# MicroMod-LoRa-1W-Function-Board.net
KiCad netlist of a schematic drawn in EAGLE
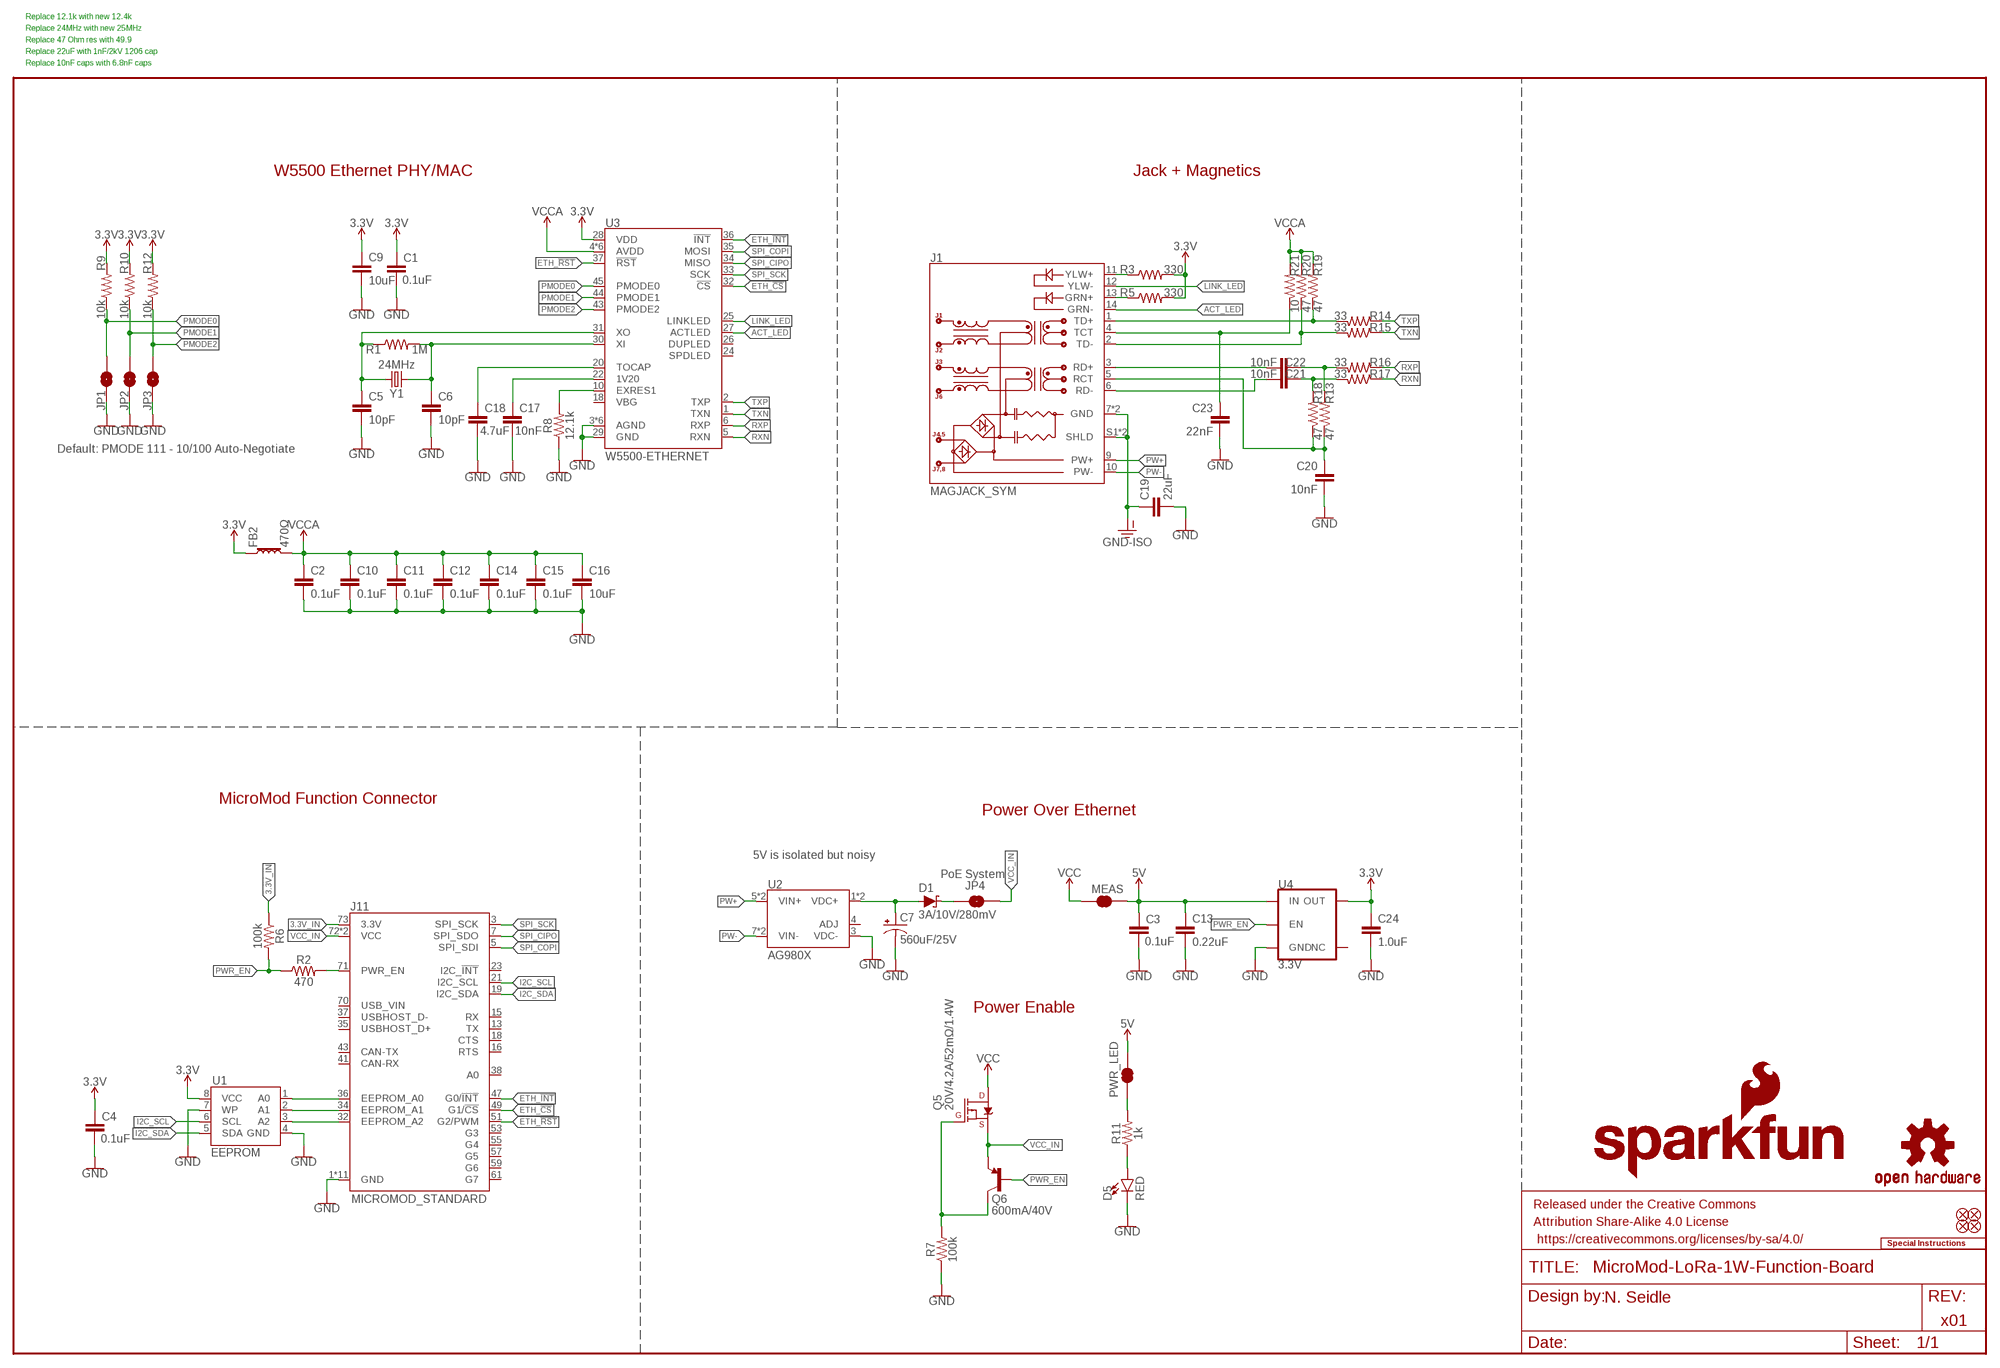
[diagram p0: schematic, sheet 1]

(export (version "E")
  (design (tool "Eeschema 10.0.6"))
  (components
    (comp (ref "C1")
      (value "0.1uF")
      (footprint "eagle-import:0603")
      (libsource (lib "eagle-import") (part "0.1UF-0603-25V-(+80/-20%)"))
    )
    (comp (ref "C2")
      (value "0.1uF")
      (footprint "eagle-import:0603")
      (libsource (lib "eagle-import") (part "0.1UF-0603-25V-5%"))
    )
    (comp (ref "C3")
      (value "0.1uF")
      (footprint "eagle-import:0603")
      (libsource (lib "eagle-import") (part "0.1UF-0603-25V-(+80/-20%)"))
    )
    (comp (ref "C4")
      (value "0.1uF")
      (footprint "eagle-import:0603")
      (libsource (lib "eagle-import") (part "0.1UF-0603-25V-(+80/-20%)"))
    )
    (comp (ref "C5")
      (value "10pF")
      (footprint "eagle-import:0603")
      (libsource (lib "eagle-import") (part "10PF-0603-50V-5%"))
    )
    (comp (ref "C6")
      (value "10pF")
      (footprint "eagle-import:0603")
      (libsource (lib "eagle-import") (part "10PF-0603-50V-5%"))
    )
    (comp (ref "C7")
      (value "560uF/25V")
      (footprint "eagle-import:PANASONIC_G")
      (libsource (lib "eagle-import") (part "560UF-PANASONIC_G-25V-20%"))
    )
    (comp (ref "C9")
      (value "10uF")
      (footprint "eagle-import:0603")
      (libsource (lib "eagle-import") (part "10UF-0603-6.3V-20%"))
    )
    (comp (ref "C10")
      (value "0.1uF")
      (footprint "eagle-import:0603")
      (libsource (lib "eagle-import") (part "0.1UF-0603-25V-5%"))
    )
    (comp (ref "C11")
      (value "0.1uF")
      (footprint "eagle-import:0603")
      (libsource (lib "eagle-import") (part "0.1UF-0603-25V-5%"))
    )
    (comp (ref "C12")
      (value "0.1uF")
      (footprint "eagle-import:0603")
      (libsource (lib "eagle-import") (part "0.1UF-0603-25V-5%"))
    )
    (comp (ref "C13")
      (value "0.22uF")
      (footprint "eagle-import:0603")
      (libsource (lib "eagle-import") (part "0.22UF-0603-25V-10%"))
    )
    (comp (ref "C14")
      (value "0.1uF")
      (footprint "eagle-import:0603")
      (libsource (lib "eagle-import") (part "0.1UF-0603-25V-5%"))
    )
    (comp (ref "C15")
      (value "0.1uF")
      (footprint "eagle-import:0603")
      (libsource (lib "eagle-import") (part "0.1UF-0603-25V-5%"))
    )
    (comp (ref "C16")
      (value "10uF")
      (footprint "eagle-import:0603")
      (libsource (lib "eagle-import") (part "10UF-0603-6.3V-20%"))
    )
    (comp (ref "C17")
      (value "10nF")
      (footprint "eagle-import:0603")
      (libsource (lib "eagle-import") (part "10NF-0603-50V-10%"))
    )
    (comp (ref "C18")
      (value "4.7uF")
      (footprint "eagle-import:0603")
      (libsource (lib "eagle-import") (part "4.7UF-0603-6.3V-(10%)"))
    )
    (comp (ref "C19")
      (value "22uF")
      (footprint "eagle-import:1206")
      (libsource (lib "eagle-import") (part "22UF-1206-50V-10%"))
    )
    (comp (ref "C20")
      (value "10nF")
      (footprint "eagle-import:0603")
      (libsource (lib "eagle-import") (part "10NF-0603-50V-10%"))
    )
    (comp (ref "C21")
      (value "10nF")
      (footprint "eagle-import:0603")
      (libsource (lib "eagle-import") (part "10NF-0603-50V-10%"))
    )
    (comp (ref "C22")
      (value "10nF")
      (footprint "eagle-import:0603")
      (libsource (lib "eagle-import") (part "10NF-0603-50V-10%"))
    )
    (comp (ref "C23")
      (value "22nF")
      (footprint "eagle-import:0603")
      (libsource (lib "eagle-import") (part "22NF/22,000PF-0603-50V-10%"))
    )
    (comp (ref "C24")
      (value "1.0uF")
      (footprint "eagle-import:0603")
      (libsource (lib "eagle-import") (part "1.0UF-0603-16V-10%-X7R"))
    )
    (comp (ref "D1")
      (value "3A/10V/280mV")
      (footprint "eagle-import:SOD-323")
      (libsource (lib "eagle-import") (part "DIODE-SCHOTTKY-BAT60A"))
    )
    (comp (ref "D5")
      (value "RED")
      (footprint "eagle-import:LED-0603")
      (libsource (lib "eagle-import") (part "LED-RED0603"))
    )
    (comp (ref "FB2")
      (value "470Ω")
      (footprint "eagle-import:0603")
      (libsource (lib "eagle-import") (part "FERRITE_BEAD-0603-470Ω-100MHZ-1A-200MILIΩ"))
    )
    (comp (ref "FD1")
      (value "FIDUCIALUFIDUCIAL")
      (footprint "eagle-import:FIDUCIAL-MICRO")
      (libsource (lib "eagle-import") (part "FIDUCIALUFIDUCIAL"))
    )
    (comp (ref "FD2")
      (value "FIDUCIALUFIDUCIAL")
      (footprint "eagle-import:FIDUCIAL-MICRO")
      (libsource (lib "eagle-import") (part "FIDUCIALUFIDUCIAL"))
    )
    (comp (ref "FD3")
      (value "FIDUCIALUFIDUCIAL")
      (footprint "eagle-import:FIDUCIAL-MICRO")
      (libsource (lib "eagle-import") (part "FIDUCIALUFIDUCIAL"))
    )
    (comp (ref "FD4")
      (value "FIDUCIALUFIDUCIAL")
      (footprint "eagle-import:FIDUCIAL-MICRO")
      (libsource (lib "eagle-import") (part "FIDUCIALUFIDUCIAL"))
    )
    (comp (ref "FRAME1")
      (value "FRAME-LEDGER")
      (footprint "eagle-import:CREATIVE_COMMONS")
      (libsource (lib "eagle-import") (part "FRAME-LEDGER"))
    )
    (comp (ref "J1")
      (value "MAGJACK_SYM")
      (footprint "eagle-import:MAGJACK-STR_LED")
      (libsource (lib "eagle-import") (part "MAGJACK_SYM"))
    )
    (comp (ref "J11")
      (value "MICROMOD_STANDARD")
      (footprint "eagle-import:M.2-CARD-E-22_FUNCTION_STANDARD")
      (libsource (lib "eagle-import") (part "MICROMOD_STANDARD"))
    )
    (comp (ref "JP1")
      (value "JUMPER-SMT_2_NO_SILK")
      (footprint "eagle-import:SMT-JUMPER_2_NO_SILK")
      (libsource (lib "eagle-import") (part "JUMPER-SMT_2_NO_SILK"))
    )
    (comp (ref "JP2")
      (value "JUMPER-SMT_2_NO_SILK")
      (footprint "eagle-import:SMT-JUMPER_2_NO_SILK")
      (libsource (lib "eagle-import") (part "JUMPER-SMT_2_NO_SILK"))
    )
    (comp (ref "JP3")
      (value "JUMPER-SMT_2_NO_SILK")
      (footprint "eagle-import:SMT-JUMPER_2_NO_SILK")
      (libsource (lib "eagle-import") (part "JUMPER-SMT_2_NO_SILK"))
    )
    (comp (ref "JP4")
      (value "PoE System")
      (footprint "eagle-import:SMT-JUMPER_2_NO_SILK")
      (libsource (lib "eagle-import") (part "JUMPER-SMT_2_NO_SILK"))
    )
    (comp (ref "LOGO1")
      (value "SFE_LOGO_NAME_FLAME.1_INCH")
      (footprint "eagle-import:SFE_LOGO_NAME_FLAME_.1")
      (libsource (lib "eagle-import") (part "SFE_LOGO_NAME_FLAME.1_INCH"))
    )
    (comp (ref "LOGO2")
      (value "SPECIAL_INSTRUCTIONS-ORDERING")
      (footprint "eagle-import:ORDERING_INSTRUCTIONS")
      (libsource (lib "eagle-import") (part "SPECIAL_INSTRUCTIONS-ORDERING"))
    )
    (comp (ref "LOGO3")
      (value "OSHW-LOGOMINI")
      (footprint "eagle-import:OSHW-LOGO-MINI")
      (libsource (lib "eagle-import") (part "OSHW-LOGOMINI"))
    )
    (comp (ref "MEAS")
      (value "JUMPER-COMBO_2_NC_TRACE")
      (footprint "eagle-import:COMBO-JUMPER_2_NC_TRACE")
      (libsource (lib "eagle-import") (part "JUMPER-COMBO_2_NC_TRACE"))
    )
    (comp (ref "PWR_LED")
      (value "JUMPER-SMT_2_NC_TRACE_SILK")
      (footprint "eagle-import:SMT-JUMPER_2_NC_TRACE_SILK")
      (libsource (lib "eagle-import") (part "JUMPER-SMT_2_NC_TRACE_SILK"))
    )
    (comp (ref "Q5")
      (value "20V/4.2A/52mΩ/1.4W")
      (footprint "eagle-import:SOT23-3")
      (libsource (lib "eagle-import") (part "MOSFET_PCH-DMG2305UX-7"))
    )
    (comp (ref "Q6")
      (value "600mA/40V")
      (footprint "eagle-import:SOT23-3")
      (libsource (lib "eagle-import") (part "TRANS_PNP-MMBT4403"))
    )
    (comp (ref "R1")
      (value "1M")
      (footprint "eagle-import:0603")
      (libsource (lib "eagle-import") (part "1MOHM-0603-1/4W-5%"))
    )
    (comp (ref "R2")
      (value "470")
      (footprint "eagle-import:0603")
      (libsource (lib "eagle-import") (part "470OHM-0603-1/10W-1%"))
    )
    (comp (ref "R3")
      (value "330")
      (footprint "eagle-import:0603")
      (libsource (lib "eagle-import") (part "330OHM-0603-1/10W-1%"))
    )
    (comp (ref "R5")
      (value "330")
      (footprint "eagle-import:0603")
      (libsource (lib "eagle-import") (part "330OHM-0603-1/10W-1%"))
    )
    (comp (ref "R6")
      (value "100k")
      (footprint "eagle-import:0603")
      (libsource (lib "eagle-import") (part "100KOHM-0603-1/10W-1%"))
    )
    (comp (ref "R7")
      (value "100k")
      (footprint "eagle-import:0603")
      (libsource (lib "eagle-import") (part "100KOHM-0603-1/10W-1%"))
    )
    (comp (ref "R8")
      (value "12.1k")
      (footprint "eagle-import:0603")
      (libsource (lib "eagle-import") (part "12.1KOHM-0603-1/10W-1%"))
    )
    (comp (ref "R9")
      (value "10k")
      (footprint "eagle-import:0603")
      (libsource (lib "eagle-import") (part "10KOHM-0603-1/10W-1%"))
    )
    (comp (ref "R10")
      (value "10k")
      (footprint "eagle-import:0603")
      (libsource (lib "eagle-import") (part "10KOHM-0603-1/10W-1%"))
    )
    (comp (ref "R11")
      (value "1k")
      (footprint "eagle-import:0603")
      (libsource (lib "eagle-import") (part "1KOHM-0603-1/10W-1%"))
    )
    (comp (ref "R12")
      (value "10k")
      (footprint "eagle-import:0603")
      (libsource (lib "eagle-import") (part "10KOHM-0603-1/10W-1%"))
    )
    (comp (ref "R13")
      (value "47")
      (footprint "eagle-import:0603")
      (libsource (lib "eagle-import") (part "47OHM-0603-1/10W-1%"))
    )
    (comp (ref "R14")
      (value "33")
      (footprint "eagle-import:0603")
      (libsource (lib "eagle-import") (part "33OHM-0603-1/10W-1%"))
    )
    (comp (ref "R15")
      (value "33")
      (footprint "eagle-import:0603")
      (libsource (lib "eagle-import") (part "33OHM-0603-1/10W-1%"))
    )
    (comp (ref "R16")
      (value "33")
      (footprint "eagle-import:0603")
      (libsource (lib "eagle-import") (part "33OHM-0603-1/10W-1%"))
    )
    (comp (ref "R17")
      (value "33")
      (footprint "eagle-import:0603")
      (libsource (lib "eagle-import") (part "33OHM-0603-1/10W-1%"))
    )
    (comp (ref "R18")
      (value "47")
      (footprint "eagle-import:0603")
      (libsource (lib "eagle-import") (part "47OHM-0603-1/10W-1%"))
    )
    (comp (ref "R19")
      (value "47")
      (footprint "eagle-import:0603")
      (libsource (lib "eagle-import") (part "47OHM-0603-1/10W-1%"))
    )
    (comp (ref "R20")
      (value "47")
      (footprint "eagle-import:0603")
      (libsource (lib "eagle-import") (part "47OHM-0603-1/10W-1%"))
    )
    (comp (ref "R21")
      (value "10")
      (footprint "eagle-import:0603")
      (libsource (lib "eagle-import") (part "10OHM-0603-1/10W-1%"))
    )
    (comp (ref "U1")
      (value "EEPROM")
      (footprint "eagle-import:SO08")
      (libsource (lib "eagle-import") (part "EEPROM-I2C512K"))
    )
    (comp (ref "U2")
      (value "AG980X")
      (footprint "eagle-import:AG980X")
      (libsource (lib "eagle-import") (part "AG980X"))
    )
    (comp (ref "U3")
      (value "W5500-ETHERNET")
      (footprint "eagle-import:LQFP-48")
      (libsource (lib "eagle-import") (part "W5500-ETHERNET"))
    )
    (comp (ref "U4")
      (value "3.3V")
      (footprint "eagle-import:SOT23-5")
      (libsource (lib "eagle-import") (part "V_REG_AP2112K-3.3V"))
    )
    (comp (ref "Y1")
      (value "24MHz")
      (footprint "eagle-import:CRYSTAL-SMD-2.0X1.6MM")
      (libsource (lib "eagle-import") (part "CRYSTAL-24MHZ-SMD-2.0X1.6MM"))
    )
  )
  (nets
    (net (code "1") (name "/ETH_~{CS}") (class "Default")
      (node (ref "J11") (pin "49") (pinfunction "G1/~{CS}_49") (pintype "bidirectional"))
      (node (ref "U3") (pin "32") (pinfunction "~{CS}_32") (pintype "bidirectional"))
    )
    (net (code "2") (name "/ETH_~{INT}") (class "Default")
      (node (ref "J11") (pin "47") (pinfunction "G0/~{INT}_47") (pintype "bidirectional"))
      (node (ref "U3") (pin "36") (pinfunction "~{INT}_36") (pintype "bidirectional"))
    )
    (net (code "3") (name "/ETH_~{RST}") (class "Default")
      (node (ref "J11") (pin "51") (pinfunction "G2/PWM_51") (pintype "bidirectional"))
      (node (ref "U3") (pin "37") (pinfunction "~{RST}_37") (pintype "bidirectional"))
    )
    (net (code "4") (name "3.3V") (class "Default")
      (node (ref "C1") (pin "1") (pinfunction "1_1") (pintype "passive"))
      (node (ref "C24") (pin "1") (pinfunction "1_1") (pintype "passive"))
      (node (ref "C4") (pin "1") (pinfunction "1_1") (pintype "passive"))
      (node (ref "C9") (pin "1") (pinfunction "1_1") (pintype "passive"))
      (node (ref "FB2") (pin "1") (pinfunction "1_1") (pintype "passive"))
      (node (ref "R10") (pin "2") (pinfunction "2_2") (pintype "passive"))
      (node (ref "R12") (pin "2") (pinfunction "2_2") (pintype "passive"))
      (node (ref "R3") (pin "2") (pinfunction "2_2") (pintype "passive"))
      (node (ref "R5") (pin "2") (pinfunction "2_2") (pintype "passive"))
      (node (ref "R9") (pin "2") (pinfunction "2_2") (pintype "passive"))
      (node (ref "U1") (pin "8") (pinfunction "VCC_8") (pintype "power_in"))
      (node (ref "U3") (pin "28") (pinfunction "VDD_28") (pintype "bidirectional"))
      (node (ref "U4") (pin "5") (pinfunction "OUT_5") (pintype "passive"))
    )
    (net (code "5") (name "3.3V_IN") (class "Default")
      (node (ref "J11") (pin "73") (pinfunction "3.3V_73") (pintype "bidirectional"))
      (node (ref "R6") (pin "1") (pinfunction "1_1") (pintype "passive"))
    )
    (net (code "6") (name "5V") (class "Default")
      (node (ref "C13") (pin "1") (pinfunction "1_1") (pintype "passive"))
      (node (ref "C3") (pin "1") (pinfunction "1_1") (pintype "passive"))
      (node (ref "MEAS") (pin "2") (pinfunction "2_2") (pintype "passive"))
      (node (ref "MEAS") (pin "4") (pinfunction "2_4") (pintype "passive"))
      (node (ref "PWR_LED") (pin "2") (pinfunction "2_2") (pintype "passive"))
      (node (ref "U4") (pin "1") (pinfunction "IN_1") (pintype "input"))
    )
    (net (code "7") (name "ACT_LED") (class "Default")
      (node (ref "J1") (pin "14") (pinfunction "GRN-_14") (pintype "bidirectional"))
      (node (ref "U3") (pin "27") (pinfunction "ACTLED_27") (pintype "bidirectional"))
    )
    (net (code "8") (name "GND") (class "Default")
      (node (ref "C1") (pin "2") (pinfunction "2_2") (pintype "passive"))
      (node (ref "C10") (pin "2") (pinfunction "2_2") (pintype "passive"))
      (node (ref "C11") (pin "2") (pinfunction "2_2") (pintype "passive"))
      (node (ref "C12") (pin "2") (pinfunction "2_2") (pintype "passive"))
      (node (ref "C13") (pin "2") (pinfunction "2_2") (pintype "passive"))
      (node (ref "C14") (pin "2") (pinfunction "2_2") (pintype "passive"))
      (node (ref "C15") (pin "2") (pinfunction "2_2") (pintype "passive"))
      (node (ref "C16") (pin "2") (pinfunction "2_2") (pintype "passive"))
      (node (ref "C17") (pin "2") (pinfunction "2_2") (pintype "passive"))
      (node (ref "C18") (pin "2") (pinfunction "2_2") (pintype "passive"))
      (node (ref "C19") (pin "2") (pinfunction "2_2") (pintype "passive"))
      (node (ref "C2") (pin "2") (pinfunction "2_2") (pintype "passive"))
      (node (ref "C20") (pin "2") (pinfunction "2_2") (pintype "passive"))
      (node (ref "C23") (pin "2") (pinfunction "2_2") (pintype "passive"))
      (node (ref "C24") (pin "2") (pinfunction "2_2") (pintype "passive"))
      (node (ref "C3") (pin "2") (pinfunction "2_2") (pintype "passive"))
      (node (ref "C4") (pin "2") (pinfunction "2_2") (pintype "passive"))
      (node (ref "C5") (pin "2") (pinfunction "2_2") (pintype "passive"))
      (node (ref "C6") (pin "2") (pinfunction "2_2") (pintype "passive"))
      (node (ref "C7") (pin "-") (pinfunction "-_-") (pintype "passive"))
      (node (ref "C9") (pin "2") (pinfunction "2_2") (pintype "passive"))
      (node (ref "D5") (pin "C") (pinfunction "C_C") (pintype "passive"))
      (node (ref "J11") (pin "1") (pinfunction "GND_1") (pintype "bidirectional"))
      (node (ref "J11") (pin "33") (pinfunction "GND_33") (pintype "bidirectional"))
      (node (ref "J11") (pin "39") (pinfunction "GND_39") (pintype "bidirectional"))
      (node (ref "J11") (pin "45") (pinfunction "GND_45") (pintype "bidirectional"))
      (node (ref "J11") (pin "75") (pinfunction "GND_75") (pintype "bidirectional"))
      (node (ref "J11") (pin "GND1") (pinfunction "GND_GND1") (pintype "bidirectional"))
      (node (ref "J11") (pin "GND2") (pinfunction "GND_GND2") (pintype "bidirectional"))
      (node (ref "J11") (pin "GND3") (pinfunction "GND_GND3") (pintype "bidirectional"))
      (node (ref "J11") (pin "GND4") (pinfunction "GND_GND4") (pintype "bidirectional"))
      (node (ref "J11") (pin "GND5") (pinfunction "GND_GND5") (pintype "bidirectional"))
      (node (ref "J11") (pin "GND6") (pinfunction "GND_GND6") (pintype "bidirectional"))
      (node (ref "JP1") (pin "1") (pinfunction "1_1") (pintype "passive"))
      (node (ref "JP2") (pin "1") (pinfunction "1_1") (pintype "passive"))
      (node (ref "JP3") (pin "1") (pinfunction "1_1") (pintype "passive"))
      (node (ref "R7") (pin "1") (pinfunction "1_1") (pintype "passive"))
      (node (ref "R8") (pin "1") (pinfunction "1_1") (pintype "passive"))
      (node (ref "U1") (pin "4") (pinfunction "GND_4") (pintype "power_in"))
      (node (ref "U1") (pin "7") (pinfunction "WP_7") (pintype "bidirectional"))
      (node (ref "U2") (pin "3") (pinfunction "VDC-_3") (pintype "bidirectional"))
      (node (ref "U3") (pin "14") (pinfunction "AGND_14") (pintype "bidirectional"))
      (node (ref "U3") (pin "16") (pinfunction "AGND_16") (pintype "bidirectional"))
      (node (ref "U3") (pin "19") (pinfunction "AGND_19") (pintype "bidirectional"))
      (node (ref "U3") (pin "29") (pinfunction "GND_29") (pintype "bidirectional"))
      (node (ref "U3") (pin "3") (pinfunction "AGND_3") (pintype "bidirectional"))
      (node (ref "U3") (pin "48") (pinfunction "AGND_48") (pintype "bidirectional"))
      (node (ref "U3") (pin "9") (pinfunction "AGND_9") (pintype "bidirectional"))
      (node (ref "U4") (pin "2") (pinfunction "GND_2") (pintype "input"))
    )
    (net (code "9") (name "GND-ISO") (class "Default")
      (node (ref "C19") (pin "1") (pinfunction "1_1") (pintype "passive"))
      (node (ref "J1") (pin "7") (pinfunction "GND_7") (pintype "bidirectional"))
      (node (ref "J1") (pin "8") (pinfunction "GND_8") (pintype "bidirectional"))
      (node (ref "J1") (pin "S1") (pinfunction "SHLD_S1") (pintype "bidirectional"))
      (node (ref "J1") (pin "S2") (pinfunction "SHLD_S2") (pintype "bidirectional"))
    )
    (net (code "10") (name "I2C_SCL") (class "Default")
      (node (ref "J11") (pin "21") (pinfunction "I2C_SCL_21") (pintype "bidirectional"))
      (node (ref "U1") (pin "6") (pinfunction "SCL_6") (pintype "bidirectional"))
    )
    (net (code "11") (name "I2C_SDA") (class "Default")
      (node (ref "J11") (pin "19") (pinfunction "I2C_SDA_19") (pintype "bidirectional"))
      (node (ref "U1") (pin "5") (pinfunction "SDA_5") (pintype "bidirectional"))
    )
    (net (code "12") (name "LINK_LED") (class "Default")
      (node (ref "J1") (pin "12") (pinfunction "YLW-_12") (pintype "bidirectional"))
      (node (ref "U3") (pin "25") (pinfunction "LINKLED_25") (pintype "bidirectional"))
    )
    (net (code "13") (name "Net-(C7-Pad+)") (class "Default")
      (node (ref "C7") (pin "+") (pinfunction "+_+") (pintype "passive"))
      (node (ref "D1") (pin "A") (pinfunction "A_A") (pintype "passive"))
      (node (ref "U2") (pin "1") (pinfunction "VDC+_1") (pintype "bidirectional"))
      (node (ref "U2") (pin "2") (pinfunction "VDC+_2") (pintype "bidirectional"))
    )
    (net (code "14") (name "Net-(C21-Pad1)") (class "Default")
      (node (ref "C21") (pin "1") (pinfunction "1_1") (pintype "passive"))
      (node (ref "R17") (pin "2") (pinfunction "2_2") (pintype "passive"))
      (node (ref "R18") (pin "2") (pinfunction "2_2") (pintype "passive"))
    )
    (net (code "15") (name "Net-(C22-Pad1)") (class "Default")
      (node (ref "C22") (pin "1") (pinfunction "1_1") (pintype "passive"))
      (node (ref "R13") (pin "2") (pinfunction "2_2") (pintype "passive"))
      (node (ref "R16") (pin "2") (pinfunction "2_2") (pintype "passive"))
    )
    (net (code "16") (name "Net-(D1-PadC)") (class "Default")
      (node (ref "D1") (pin "C") (pinfunction "C_C") (pintype "passive"))
      (node (ref "JP4") (pin "1") (pinfunction "1_1") (pintype "passive"))
    )
    (net (code "17") (name "Net-(D5-PadA)") (class "Default")
      (node (ref "D5") (pin "A") (pinfunction "A_A") (pintype "passive"))
      (node (ref "R11") (pin "1") (pinfunction "1_1") (pintype "passive"))
    )
    (net (code "18") (name "Net-(J1-GRN+)") (class "Default")
      (node (ref "J1") (pin "13") (pinfunction "GRN+_13") (pintype "bidirectional"))
      (node (ref "R5") (pin "1") (pinfunction "1_1") (pintype "passive"))
    )
    (net (code "19") (name "Net-(J1-RCT)") (class "Default")
      (node (ref "C20") (pin "1") (pinfunction "1_1") (pintype "passive"))
      (node (ref "J1") (pin "5") (pinfunction "RCT_5") (pintype "bidirectional"))
      (node (ref "R13") (pin "1") (pinfunction "1_1") (pintype "passive"))
      (node (ref "R18") (pin "1") (pinfunction "1_1") (pintype "passive"))
    )
    (net (code "20") (name "Net-(J1-RD+)") (class "Default")
      (node (ref "C22") (pin "2") (pinfunction "2_2") (pintype "passive"))
      (node (ref "J1") (pin "3") (pinfunction "RD+_3") (pintype "bidirectional"))
    )
    (net (code "21") (name "Net-(J1-RD-)") (class "Default")
      (node (ref "C21") (pin "2") (pinfunction "2_2") (pintype "passive"))
      (node (ref "J1") (pin "6") (pinfunction "RD-_6") (pintype "bidirectional"))
    )
    (net (code "22") (name "Net-(J1-TCT)") (class "Default")
      (node (ref "C23") (pin "1") (pinfunction "1_1") (pintype "passive"))
      (node (ref "J1") (pin "4") (pinfunction "TCT_4") (pintype "bidirectional"))
      (node (ref "R21") (pin "1") (pinfunction "1_1") (pintype "passive"))
    )
    (net (code "23") (name "Net-(J1-TD+)") (class "Default")
      (node (ref "J1") (pin "1") (pinfunction "TD+_1") (pintype "bidirectional"))
      (node (ref "R14") (pin "2") (pinfunction "2_2") (pintype "passive"))
      (node (ref "R19") (pin "1") (pinfunction "1_1") (pintype "passive"))
    )
    (net (code "24") (name "Net-(J1-TD-)") (class "Default")
      (node (ref "J1") (pin "2") (pinfunction "TD-_2") (pintype "bidirectional"))
      (node (ref "R15") (pin "2") (pinfunction "2_2") (pintype "passive"))
      (node (ref "R20") (pin "1") (pinfunction "1_1") (pintype "passive"))
    )
    (net (code "25") (name "Net-(J1-YLW+)") (class "Default")
      (node (ref "J1") (pin "11") (pinfunction "YLW+_11") (pintype "bidirectional"))
      (node (ref "R3") (pin "1") (pinfunction "1_1") (pintype "passive"))
    )
    (net (code "26") (name "Net-(J11-EEPROM_A0)") (class "Default")
      (node (ref "J11") (pin "36") (pinfunction "EEPROM_A0_36") (pintype "bidirectional"))
      (node (ref "U1") (pin "1") (pinfunction "A0_1") (pintype "bidirectional"))
    )
    (net (code "27") (name "Net-(J11-EEPROM_A1)") (class "Default")
      (node (ref "J11") (pin "34") (pinfunction "EEPROM_A1_34") (pintype "bidirectional"))
      (node (ref "U1") (pin "2") (pinfunction "A1_2") (pintype "bidirectional"))
    )
    (net (code "28") (name "Net-(J11-EEPROM_A2)") (class "Default")
      (node (ref "J11") (pin "32") (pinfunction "EEPROM_A2_32") (pintype "bidirectional"))
      (node (ref "U1") (pin "3") (pinfunction "A2_3") (pintype "bidirectional"))
    )
    (net (code "29") (name "Net-(J11-PWR_EN)") (class "Default")
      (node (ref "J11") (pin "71") (pinfunction "PWR_EN_71") (pintype "bidirectional"))
      (node (ref "R2") (pin "2") (pinfunction "2_2") (pintype "passive"))
    )
    (net (code "30") (name "Net-(PWR_LED-Pad1)") (class "Default")
      (node (ref "PWR_LED") (pin "1") (pinfunction "1_1") (pintype "passive"))
      (node (ref "R11") (pin "2") (pinfunction "2_2") (pintype "passive"))
    )
    (net (code "31") (name "Net-(Q5-G)") (class "Default")
      (node (ref "Q5") (pin "1") (pinfunction "G_1") (pintype "bidirectional"))
      (node (ref "Q6") (pin "3") (pinfunction "C_3") (pintype "passive"))
      (node (ref "R7") (pin "2") (pinfunction "2_2") (pintype "passive"))
    )
    (net (code "32") (name "Net-(U3-1V20)") (class "Default")
      (node (ref "C17") (pin "1") (pinfunction "1_1") (pintype "passive"))
      (node (ref "U3") (pin "22") (pinfunction "1V20_22") (pintype "bidirectional"))
    )
    (net (code "33") (name "Net-(U3-EXRES1)") (class "Default")
      (node (ref "R8") (pin "2") (pinfunction "2_2") (pintype "passive"))
      (node (ref "U3") (pin "10") (pinfunction "EXRES1_10") (pintype "bidirectional"))
    )
    (net (code "34") (name "Net-(U3-TOCAP)") (class "Default")
      (node (ref "C18") (pin "1") (pinfunction "1_1") (pintype "passive"))
      (node (ref "U3") (pin "20") (pinfunction "TOCAP_20") (pintype "bidirectional"))
    )
    (net (code "35") (name "Net-(U3-XI)") (class "Default")
      (node (ref "C6") (pin "1") (pinfunction "1_1") (pintype "passive"))
      (node (ref "R1") (pin "2") (pinfunction "2_2") (pintype "passive"))
      (node (ref "U3") (pin "30") (pinfunction "XI_30") (pintype "bidirectional"))
      (node (ref "Y1") (pin "3") (pinfunction "2_3") (pintype "passive"))
    )
    (net (code "36") (name "Net-(U3-XO)") (class "Default")
      (node (ref "C5") (pin "1") (pinfunction "1_1") (pintype "passive"))
      (node (ref "R1") (pin "1") (pinfunction "1_1") (pintype "passive"))
      (node (ref "U3") (pin "31") (pinfunction "XO_31") (pintype "bidirectional"))
      (node (ref "Y1") (pin "1") (pinfunction "1_1") (pintype "passive"))
    )
    (net (code "37") (name "PMODE0") (class "Default")
      (node (ref "JP1") (pin "2") (pinfunction "2_2") (pintype "passive"))
      (node (ref "R9") (pin "1") (pinfunction "1_1") (pintype "passive"))
      (node (ref "U3") (pin "45") (pinfunction "PMODE0_45") (pintype "bidirectional"))
    )
    (net (code "38") (name "PMODE1") (class "Default")
      (node (ref "JP2") (pin "2") (pinfunction "2_2") (pintype "passive"))
      (node (ref "R10") (pin "1") (pinfunction "1_1") (pintype "passive"))
      (node (ref "U3") (pin "44") (pinfunction "PMODE1_44") (pintype "bidirectional"))
    )
    (net (code "39") (name "PMODE2") (class "Default")
      (node (ref "JP3") (pin "2") (pinfunction "2_2") (pintype "passive"))
      (node (ref "R12") (pin "1") (pinfunction "1_1") (pintype "passive"))
      (node (ref "U3") (pin "43") (pinfunction "PMODE2_43") (pintype "bidirectional"))
    )
    (net (code "40") (name "PW+") (class "Default")
      (node (ref "J1") (pin "9") (pinfunction "PW+_9") (pintype "bidirectional"))
      (node (ref "U2") (pin "5") (pinfunction "VIN+_5") (pintype "bidirectional"))
      (node (ref "U2") (pin "6") (pinfunction "VIN+_6") (pintype "bidirectional"))
    )
    (net (code "41") (name "PW-") (class "Default")
      (node (ref "J1") (pin "10") (pinfunction "PW-_10") (pintype "bidirectional"))
      (node (ref "U2") (pin "7") (pinfunction "VIN-_7") (pintype "bidirectional"))
      (node (ref "U2") (pin "8") (pinfunction "VIN-_8") (pintype "bidirectional"))
    )
    (net (code "42") (name "PWR_EN") (class "Default")
      (node (ref "Q6") (pin "1") (pinfunction "B_1") (pintype "passive"))
      (node (ref "R2") (pin "1") (pinfunction "1_1") (pintype "passive"))
      (node (ref "R6") (pin "2") (pinfunction "2_2") (pintype "passive"))
      (node (ref "U4") (pin "3") (pinfunction "EN_3") (pintype "input"))
    )
    (net (code "43") (name "RXN") (class "Default")
      (node (ref "R17") (pin "1") (pinfunction "1_1") (pintype "passive"))
      (node (ref "U3") (pin "5") (pinfunction "RXN_5") (pintype "bidirectional"))
    )
    (net (code "44") (name "RXP") (class "Default")
      (node (ref "R16") (pin "1") (pinfunction "1_1") (pintype "passive"))
      (node (ref "U3") (pin "6") (pinfunction "RXP_6") (pintype "bidirectional"))
    )
    (net (code "45") (name "SPI_CIPO") (class "Default")
      (node (ref "J11") (pin "7") (pinfunction "SPI_SDO_7") (pintype "bidirectional"))
      (node (ref "U3") (pin "34") (pinfunction "MISO_34") (pintype "bidirectional"))
    )
    (net (code "46") (name "SPI_COPI") (class "Default")
      (node (ref "J11") (pin "5") (pinfunction "SPI_SDI_5") (pintype "bidirectional"))
      (node (ref "U3") (pin "35") (pinfunction "MOSI_35") (pintype "bidirectional"))
    )
    (net (code "47") (name "SPI_SCK") (class "Default")
      (node (ref "J11") (pin "3") (pinfunction "SPI_SCK_3") (pintype "bidirectional"))
      (node (ref "U3") (pin "33") (pinfunction "SCK_33") (pintype "bidirectional"))
    )
    (net (code "48") (name "TXN") (class "Default")
      (node (ref "R15") (pin "1") (pinfunction "1_1") (pintype "passive"))
      (node (ref "U3") (pin "1") (pinfunction "TXN_1") (pintype "bidirectional"))
    )
    (net (code "49") (name "TXP") (class "Default")
      (node (ref "R14") (pin "1") (pinfunction "1_1") (pintype "passive"))
      (node (ref "U3") (pin "2") (pinfunction "TXP_2") (pintype "bidirectional"))
    )
    (net (code "50") (name "VCC") (class "Default")
      (node (ref "MEAS") (pin "1") (pinfunction "1_1") (pintype "passive"))
      (node (ref "MEAS") (pin "3") (pinfunction "1_3") (pintype "passive"))
      (node (ref "Q5") (pin "3") (pinfunction "D_3") (pintype "bidirectional"))
    )
    (net (code "51") (name "VCCA") (class "Default")
      (node (ref "C10") (pin "1") (pinfunction "1_1") (pintype "passive"))
      (node (ref "C11") (pin "1") (pinfunction "1_1") (pintype "passive"))
      (node (ref "C12") (pin "1") (pinfunction "1_1") (pintype "passive"))
      (node (ref "C14") (pin "1") (pinfunction "1_1") (pintype "passive"))
      (node (ref "C15") (pin "1") (pinfunction "1_1") (pintype "passive"))
      (node (ref "C16") (pin "1") (pinfunction "1_1") (pintype "passive"))
      (node (ref "C2") (pin "1") (pinfunction "1_1") (pintype "passive"))
      (node (ref "FB2") (pin "2") (pinfunction "2_2") (pintype "passive"))
      (node (ref "R19") (pin "2") (pinfunction "2_2") (pintype "passive"))
      (node (ref "R20") (pin "2") (pinfunction "2_2") (pintype "passive"))
      (node (ref "R21") (pin "2") (pinfunction "2_2") (pintype "passive"))
      (node (ref "U3") (pin "11") (pinfunction "AVDD_11") (pintype "bidirectional"))
      (node (ref "U3") (pin "15") (pinfunction "AVDD_15") (pintype "bidirectional"))
      (node (ref "U3") (pin "17") (pinfunction "AVDD_17") (pintype "bidirectional"))
      (node (ref "U3") (pin "21") (pinfunction "AVDD_21") (pintype "bidirectional"))
      (node (ref "U3") (pin "4") (pinfunction "AVDD_4") (pintype "bidirectional"))
      (node (ref "U3") (pin "8") (pinfunction "AVDD_8") (pintype "bidirectional"))
    )
    (net (code "52") (name "VCC_IN") (class "Default")
      (node (ref "J11") (pin "72") (pinfunction "VCC_72") (pintype "bidirectional"))
      (node (ref "J11") (pin "74") (pinfunction "VCC_74") (pintype "bidirectional"))
      (node (ref "JP4") (pin "2") (pinfunction "2_2") (pintype "passive"))
      (node (ref "Q5") (pin "2") (pinfunction "S_2") (pintype "bidirectional"))
      (node (ref "Q6") (pin "2") (pinfunction "E_2") (pintype "passive"))
    )
    (net (code "53") (name "unconnected-(J11-A0-Pad38)") (class "Default")
      (node (ref "J11") (pin "38") (pinfunction "A0_38") (pintype "bidirectional"))
    )
    (net (code "54") (name "unconnected-(J11-CAN-RX-Pad41)") (class "Default")
      (node (ref "J11") (pin "41") (pinfunction "CAN-RX_41") (pintype "bidirectional"))
    )
    (net (code "55") (name "unconnected-(J11-CAN-TX-Pad43)") (class "Default")
      (node (ref "J11") (pin "43") (pinfunction "CAN-TX_43") (pintype "bidirectional"))
    )
    (net (code "56") (name "unconnected-(J11-CTS-Pad18)") (class "Default")
      (node (ref "J11") (pin "18") (pinfunction "CTS_18") (pintype "bidirectional"))
    )
    (net (code "57") (name "unconnected-(J11-G3-Pad53)") (class "Default")
      (node (ref "J11") (pin "53") (pinfunction "G3_53") (pintype "bidirectional"))
    )
    (net (code "58") (name "unconnected-(J11-G4-Pad55)") (class "Default")
      (node (ref "J11") (pin "55") (pinfunction "G4_55") (pintype "bidirectional"))
    )
    (net (code "59") (name "unconnected-(J11-G5-Pad57)") (class "Default")
      (node (ref "J11") (pin "57") (pinfunction "G5_57") (pintype "bidirectional"))
    )
    (net (code "60") (name "unconnected-(J11-G6-Pad59)") (class "Default")
      (node (ref "J11") (pin "59") (pinfunction "G6_59") (pintype "bidirectional"))
    )
    (net (code "61") (name "unconnected-(J11-G7-Pad61)") (class "Default")
      (node (ref "J11") (pin "61") (pinfunction "G7_61") (pintype "bidirectional"))
    )
    (net (code "62") (name "unconnected-(J11-I2C_~{INT}-Pad23)") (class "Default")
      (node (ref "J11") (pin "23") (pinfunction "I2C_~{INT}_23") (pintype "bidirectional"))
    )
    (net (code "63") (name "unconnected-(J11-RTS-Pad16)") (class "Default")
      (node (ref "J11") (pin "16") (pinfunction "RTS_16") (pintype "bidirectional"))
    )
    (net (code "64") (name "unconnected-(J11-RX-Pad15)") (class "Default")
      (node (ref "J11") (pin "15") (pinfunction "RX_15") (pintype "bidirectional"))
    )
    (net (code "65") (name "unconnected-(J11-TX-Pad13)") (class "Default")
      (node (ref "J11") (pin "13") (pinfunction "TX_13") (pintype "bidirectional"))
    )
    (net (code "66") (name "unconnected-(J11-USBHOST_D+-Pad35)") (class "Default")
      (node (ref "J11") (pin "35") (pinfunction "USBHOST_D+_35") (pintype "bidirectional"))
    )
    (net (code "67") (name "unconnected-(J11-USBHOST_D--Pad37)") (class "Default")
      (node (ref "J11") (pin "37") (pinfunction "USBHOST_D-_37") (pintype "bidirectional"))
    )
    (net (code "68") (name "unconnected-(J11-USB_VIN-Pad70)") (class "Default")
      (node (ref "J11") (pin "70") (pinfunction "USB_VIN_70") (pintype "bidirectional"))
    )
    (net (code "69") (name "unconnected-(U2-ADJ-Pad4)") (class "Default")
      (node (ref "U2") (pin "4") (pinfunction "ADJ_4") (pintype "bidirectional"))
    )
    (net (code "70") (name "unconnected-(U3-DUPLED-Pad26)") (class "Default")
      (node (ref "U3") (pin "26") (pinfunction "DUPLED_26") (pintype "bidirectional"))
    )
    (net (code "71") (name "unconnected-(U3-SPDLED-Pad24)") (class "Default")
      (node (ref "U3") (pin "24") (pinfunction "SPDLED_24") (pintype "bidirectional"))
    )
    (net (code "72") (name "unconnected-(U3-VBG-Pad18)") (class "Default")
      (node (ref "U3") (pin "18") (pinfunction "VBG_18") (pintype "bidirectional"))
    )
    (net (code "73") (name "unconnected-(U4-NC-Pad4)") (class "Default")
      (node (ref "U4") (pin "4") (pinfunction "NC_4") (pintype "no_connect"))
    )
  )
)
